# icaRUSv0_2.net
KiCad netlist of a schematic drawn in Altium Designer
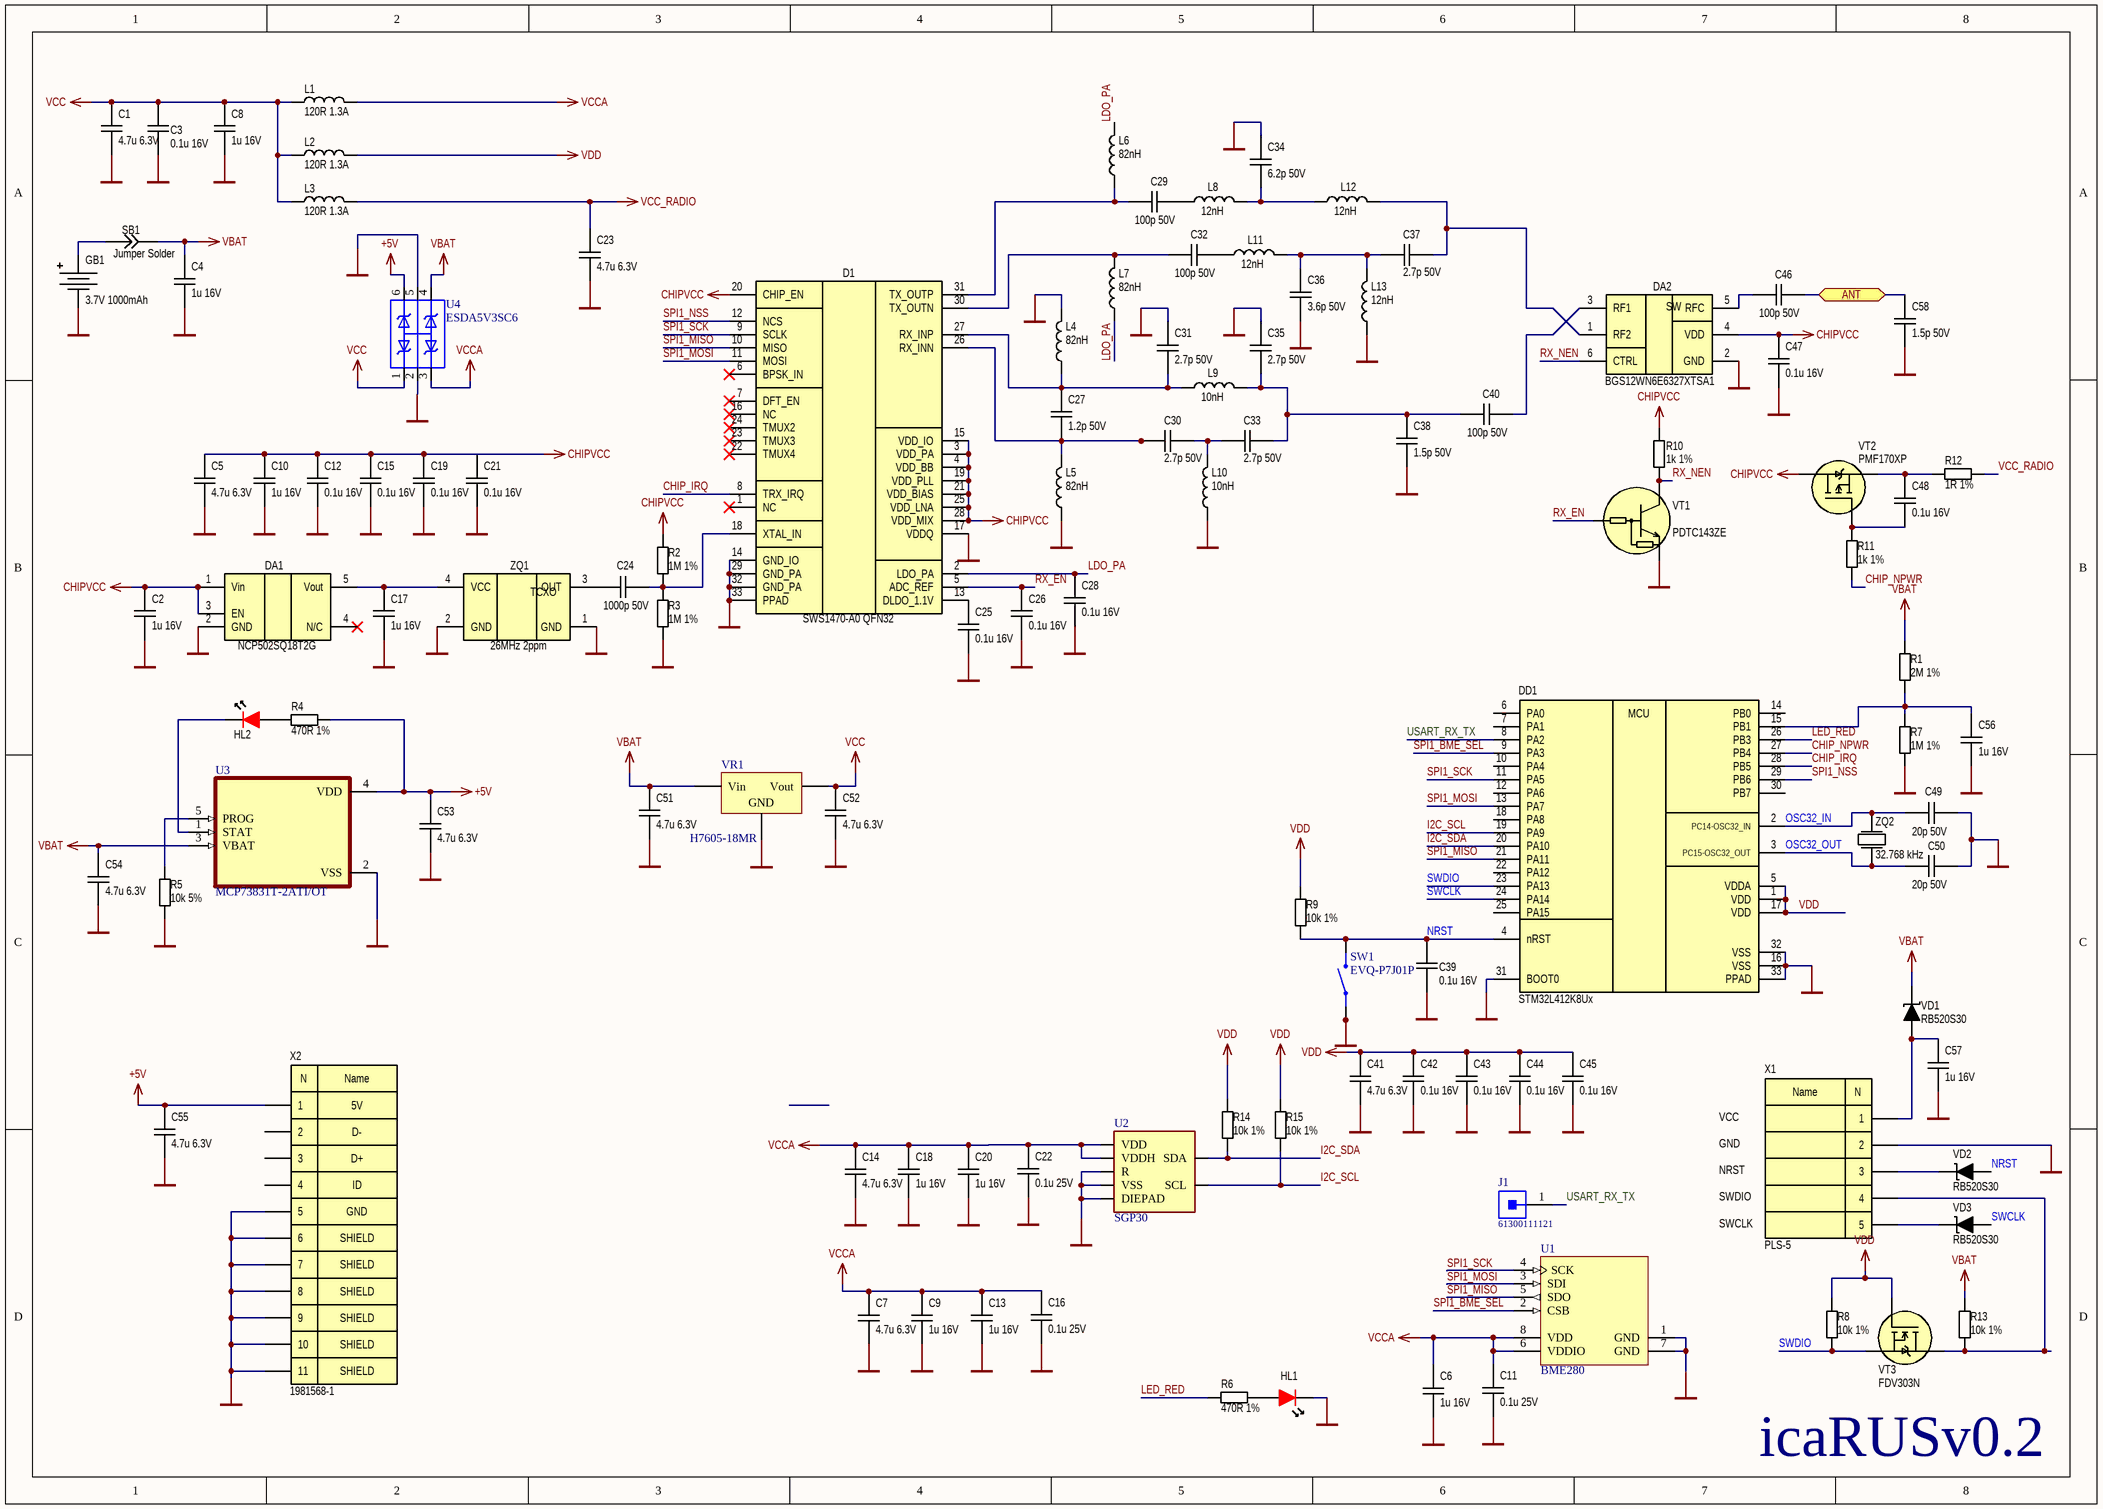
[diagram p0: icaRUSv0.2.SchDoc]

(export (version "E")
  (design (tool "Eeschema 10.0.6"))
  (components
    (comp (ref "C1")
      (value "4.7u 6.3V")
      (footprint "C0402")
      (description "CAP CER 4.7UF 6.3V X5R 0402")
      (fields (field (name "PARTNUMBER") "CC0402KRX5R5BB475"))
      (libsource (lib "Capacitors") (part "CC0402KRX5R5BB475"))
    )
    (comp (ref "C2")
      (value "1u 16V")
      (footprint "C0402")
      (description "CAP CER 1UF 16V X5R 0402")
      (fields (field (name "PARTNUMBER") "CC0402KRX5R7BB105"))
      (libsource (lib "Capacitors") (part "CC0402KRX5R7BB105"))
    )
    (comp (ref "C3")
      (value "0.1u 16V")
      (footprint "C0402")
      (description "CERCAP 0.1/16V 0402 KX7R")
      (fields (field (name "PARTNUMBER") "CC0402KRX7R7BB104"))
      (libsource (lib "Capacitors") (part "CC0603KRX7R7BB104"))
    )
    (comp (ref "C4")
      (value "1u 16V")
      (footprint "C0402")
      (description "CAP CER 1UF 16V X5R 0402")
      (fields (field (name "PARTNUMBER") "CC0402KRX5R7BB105"))
      (libsource (lib "Capacitors") (part "CC0603KRX7R7BB105"))
    )
    (comp (ref "C5")
      (value "4.7u 6.3V")
      (footprint "C0402")
      (description "CAP CER 4.7UF 6.3V X5R 0402")
      (fields (field (name "PARTNUMBER") "CC0402KRX5R5BB475"))
      (libsource (lib "Capacitors") (part "CC0402KRX5R5BB475"))
    )
    (comp (ref "C6")
      (value "1u 16V")
      (footprint "C0402")
      (description "CAP CER 1UF 16V X5R 0402")
      (fields (field (name "PARTNUMBER") "CC0402KRX5R7BB105"))
      (libsource (lib "Capacitors") (part "CC0402KRX7R8BB104"))
    )
    (comp (ref "C7")
      (value "4.7u 6.3V")
      (footprint "C0402")
      (description "CAP CER 4.7UF 6.3V X5R 0402")
      (fields (field (name "PARTNUMBER") "CC0402KRX5R5BB475"))
      (libsource (lib "Capacitors") (part "CC0402KRX5R5BB475"))
    )
    (comp (ref "C8")
      (value "1u 16V")
      (footprint "C0402")
      (description "CAP CER 1UF 16V X5R 0402")
      (fields (field (name "PARTNUMBER") "CC0402KRX5R7BB105"))
      (libsource (lib "Capacitors") (part "CC0603KRX7R7BB105"))
    )
    (comp (ref "C9")
      (value "1u 16V")
      (footprint "C0402")
      (description "CAP CER 1UF 16V X5R 0402")
      (fields (field (name "PARTNUMBER") "CC0402KRX5R7BB105"))
      (libsource (lib "Capacitors") (part "CC0402KRX7R8BB104"))
    )
    (comp (ref "C10")
      (value "1u 16V")
      (footprint "C0402")
      (description "CAP CER 1UF 16V X5R 0402")
      (fields (field (name "PARTNUMBER") "CC0402KRX5R7BB105"))
      (libsource (lib "Capacitors") (part "CC0402KRX7R8BB104"))
    )
    (comp (ref "C11")
      (value "0.1u 25V")
      (footprint "C0402")
      (description "CAP CER 0.1UF 25V X7R 0402")
      (fields (field (name "PARTNUMBER") "CC0402KRX7R8BB104"))
      (libsource (lib "Capacitors") (part "CC0402KRX7R8BB104"))
    )
    (comp (ref "C12")
      (value "0.1u 16V")
      (footprint "C0402")
      (description "CERCAP 0.1/16V 0402 KX7R")
      (fields (field (name "PARTNUMBER") "CC0402KRX7R7BB104"))
      (libsource (lib "Capacitors") (part "CC0402KRX7R8BB104"))
    )
    (comp (ref "C13")
      (value "1u 16V")
      (footprint "C0402")
      (description "CAP CER 1UF 16V X5R 0402")
      (fields (field (name "PARTNUMBER") "CC0402KRX5R7BB105"))
      (libsource (lib "Capacitors") (part "CC0402KRX7R8BB104"))
    )
    (comp (ref "C14")
      (value "4.7u 6.3V")
      (footprint "C0402")
      (description "CAP CER 4.7UF 6.3V X5R 0402")
      (fields (field (name "PARTNUMBER") "CC0402KRX5R5BB475"))
      (libsource (lib "Capacitors") (part "CC0402KRX5R5BB475"))
    )
    (comp (ref "C15")
      (value "0.1u 16V")
      (footprint "C0402")
      (description "CERCAP 0.1/16V 0402 KX7R")
      (fields (field (name "PARTNUMBER") "CC0402KRX7R7BB104"))
      (libsource (lib "Capacitors") (part "CC0402KRX7R8BB104"))
    )
    (comp (ref "C16")
      (value "0.1u 25V")
      (footprint "C0402")
      (description "CAP CER 0.1UF 25V X7R 0402")
      (fields (field (name "PARTNUMBER") "CC0402KRX7R8BB104"))
      (libsource (lib "Capacitors") (part "CC0402KRX7R8BB104"))
    )
    (comp (ref "C17")
      (value "1u 16V")
      (footprint "C0402")
      (description "CAP CER 1UF 16V X5R 0402")
      (fields (field (name "PARTNUMBER") "CC0402KRX5R7BB105"))
      (libsource (lib "Capacitors") (part "CC0402KRX5R7BB105"))
    )
    (comp (ref "C18")
      (value "1u 16V")
      (footprint "C0402")
      (description "CAP CER 1UF 16V X5R 0402")
      (fields (field (name "PARTNUMBER") "CC0402KRX5R7BB105"))
      (libsource (lib "Capacitors") (part "CC0402KRX7R8BB104"))
    )
    (comp (ref "C19")
      (value "0.1u 16V")
      (footprint "C0402")
      (description "CERCAP 0.1/16V 0402 KX7R")
      (fields (field (name "PARTNUMBER") "CC0402KRX7R7BB104"))
      (libsource (lib "Capacitors") (part "CC0402KRX7R8BB104"))
    )
    (comp (ref "C20")
      (value "1u 16V")
      (footprint "C0402")
      (description "CAP CER 1UF 16V X5R 0402")
      (fields (field (name "PARTNUMBER") "CC0402KRX5R7BB105"))
      (libsource (lib "Capacitors") (part "CC0402KRX7R8BB104"))
    )
    (comp (ref "C21")
      (value "0.1u 16V")
      (footprint "C0402")
      (description "CERCAP 0.1/16V 0402 KX7R")
      (fields (field (name "PARTNUMBER") "CC0402KRX7R7BB104"))
      (libsource (lib "Capacitors") (part "CC0402KRX7R8BB104"))
    )
    (comp (ref "C22")
      (value "0.1u 25V")
      (footprint "C0402")
      (description "CAP CER 0.1UF 25V X7R 0402")
      (fields (field (name "PARTNUMBER") "CC0402KRX7R8BB104"))
      (libsource (lib "Capacitors") (part "CC0402KRX7R8BB104"))
    )
    (comp (ref "C23")
      (value "4.7u 6.3V")
      (footprint "C0402")
      (description "CAP CER 4.7UF 6.3V X5R 0402")
      (fields (field (name "PARTNUMBER") "CC0402KRX5R5BB475"))
      (libsource (lib "Capacitors") (part "CC0402KRX5R5BB475"))
    )
    (comp (ref "C24")
      (value "1000p 50V")
      (footprint "C0402")
      (description "CAP CER 1000PF 1% 50V C0G/NPO 0402")
      (fields (field (name "PARTNUMBER") "0402N102F500LT"))
      (libsource (lib "Capacitors") (part "CC0402JRX7R9BB102"))
    )
    (comp (ref "C25")
      (value "0.1u 16V")
      (footprint "C0402")
      (description "CERCAP 0.1/16V 0402 KX7R")
      (fields (field (name "PARTNUMBER") "CC0402KRX7R7BB104"))
      (libsource (lib "Capacitors") (part "CC0402KRX7R8BB104"))
    )
    (comp (ref "C26")
      (value "0.1u 16V")
      (footprint "C0402")
      (description "CERCAP 0.1/16V 0402 KX7R")
      (fields (field (name "PARTNUMBER") "CC0402KRX7R7BB104"))
      (libsource (lib "Capacitors") (part "CC0402KRX7R8BB104"))
    )
    (comp (ref "C27")
      (value "1.2p 50V")
      (footprint "C0402")
      (description "CAP CER 1.2PF 50V NPO 0402")
      (fields (field (name "PARTNUMBER") "CC0402BRNPO9BN1R2"))
      (libsource (lib "Capacitors") (part "CC0402BRNPO9BN1R0"))
    )
    (comp (ref "C28")
      (value "0.1u 16V")
      (footprint "C0402")
      (description "CERCAP 0.1/16V 0402 KX7R")
      (fields (field (name "PARTNUMBER") "CC0402KRX7R7BB104"))
      (libsource (lib "Capacitors") (part "CC0402KRX7R8BB104"))
    )
    (comp (ref "C29")
      (value "100p 50V")
      (footprint "C0402")
      (description "CAP CER 100PF 50V C0G/NPO 0402")
      (fields (field (name "PARTNUMBER") "CC0402JRNPO9BN101"))
      (libsource (lib "Capacitors") (part "CC0402JRNPO9BN101"))
    )
    (comp (ref "C30")
      (value "2.7p 50V")
      (footprint "C0402")
      (description "CAP CER 2.7PF 50V C0G/NPO 0402")
      (fields (field (name "PARTNUMBER") "CC0402BRNPO9BN2R7"))
      (libsource (lib "Capacitors") (part "CC0402BRNPO9BN2R0"))
    )
    (comp (ref "C31")
      (value "2.7p 50V")
      (footprint "C0402")
      (description "CAP CER 2.7PF 50V C0G/NPO 0402")
      (fields (field (name "PARTNUMBER") "CC0402BRNPO9BN2R7"))
      (libsource (lib "Capacitors") (part "CC0402BRNPO9BN2R0"))
    )
    (comp (ref "C32")
      (value "100p 50V")
      (footprint "C0402")
      (description "CAP CER 100PF 50V C0G/NPO 0402")
      (fields (field (name "PARTNUMBER") "CC0402JRNPO9BN101"))
      (libsource (lib "Capacitors") (part "CC0402JRNPO9BN101"))
    )
    (comp (ref "C33")
      (value "2.7p 50V")
      (footprint "C0402")
      (description "CAP CER 2.7PF 50V C0G/NPO 0402")
      (fields (field (name "PARTNUMBER") "CC0402BRNPO9BN2R7"))
      (libsource (lib "Capacitors") (part "CC0402BRNPO9BN2R0"))
    )
    (comp (ref "C34")
      (value "6.2p 50V")
      (footprint "C0402")
      (description "CAP CER 6.2PF 50V NPO 0402")
      (fields (field (name "PARTNUMBER") "CC0402CRNPO9BN6R2"))
      (libsource (lib "Capacitors") (part "CC0402CRNPO9BN6R2"))
    )
    (comp (ref "C35")
      (value "2.7p 50V")
      (footprint "C0402")
      (description "CAP CER 2.7PF 50V C0G/NPO 0402")
      (fields (field (name "PARTNUMBER") "CC0402BRNPO9BN2R7"))
      (libsource (lib "Capacitors") (part "CC0402BRNPO9BN2R0"))
    )
    (comp (ref "C36")
      (value "3.6p 50V")
      (footprint "C0402")
      (description "CAP CER 3.6PF 50V NPO 0402")
      (fields (field (name "PARTNUMBER") "CC0402BRNPO9BN3R6"))
      (libsource (lib "Capacitors") (part "CC0402BRNPO9BN3R6"))
    )
    (comp (ref "C37")
      (value "2.7p 50V")
      (footprint "C0402")
      (description "CAP CER 2.7pF 50V NPO 0402")
      (fields (field (name "PARTNUMBER") "CC0402BRNPO9BN2R7"))
      (libsource (lib "Capacitors") (part "CC0402BRNPO9BN3R6"))
    )
    (comp (ref "C38")
      (value "1.5p 50V")
      (footprint "C0402")
      (description "CAP CER 1.5PF 50V NPO 0402")
      (fields (field (name "PARTNUMBER") "CC0402BRNPO9BN1R5"))
      (libsource (lib "Capacitors") (part "CC0402BRNPO9BN1R0"))
    )
    (comp (ref "C39")
      (value "0.1u 16V")
      (footprint "C0402")
      (description "CERCAP 0.1/16V 0402 KX7R")
      (fields (field (name "PARTNUMBER") "CC0402KRX7R7BB104"))
      (libsource (lib "Capacitors") (part "CC0402KRX7R8BB104"))
    )
    (comp (ref "C40")
      (value "100p 50V")
      (footprint "C0402")
      (description "CAP CER 100PF 50V C0G/NPO 0402")
      (fields (field (name "PARTNUMBER") "CC0402JRNPO9BN101"))
      (libsource (lib "Capacitors") (part "CC0402JRNPO9BN101"))
    )
    (comp (ref "C41")
      (value "4.7u 6.3V")
      (footprint "C0402")
      (description "CAP CER 4.7UF 6.3V X5R 0402")
      (fields (field (name "PARTNUMBER") "CC0402KRX5R5BB475"))
      (libsource (lib "Capacitors") (part "CC0402KRX5R5BB475"))
    )
    (comp (ref "C42")
      (value "0.1u 16V")
      (footprint "C0402")
      (description "CERCAP 0.1/16V 0402 KX7R")
      (fields (field (name "PARTNUMBER") "CC0402KRX7R7BB104"))
      (libsource (lib "Capacitors") (part "CC0402KRX7R8BB104"))
    )
    (comp (ref "C43")
      (value "0.1u 16V")
      (footprint "C0402")
      (description "CERCAP 0.1/16V 0402 KX7R")
      (fields (field (name "PARTNUMBER") "CC0402KRX7R7BB104"))
      (libsource (lib "Capacitors") (part "CC0402KRX7R8BB104"))
    )
    (comp (ref "C44")
      (value "0.1u 16V")
      (footprint "C0402")
      (description "CERCAP 0.1/16V 0402 KX7R")
      (fields (field (name "PARTNUMBER") "CC0402KRX7R7BB104"))
      (libsource (lib "Capacitors") (part "CC0402KRX7R8BB104"))
    )
    (comp (ref "C45")
      (value "0.1u 16V")
      (footprint "C0402")
      (description "CERCAP 0.1/16V 0402 KX7R")
      (fields (field (name "PARTNUMBER") "CC0402KRX7R7BB104"))
      (libsource (lib "Capacitors") (part "CC0402KRX7R8BB104"))
    )
    (comp (ref "C46")
      (value "100p 50V")
      (footprint "C0402")
      (description "CAP CER 100PF 50V C0G/NPO 0402")
      (fields (field (name "PARTNUMBER") "CC0402JRNPO9BN101"))
      (libsource (lib "Capacitors") (part "CC0402JRNPO9BN101"))
    )
    (comp (ref "C47")
      (value "0.1u 16V")
      (footprint "C0402")
      (description "CERCAP 0.1/16V 0402 KX7R")
      (fields (field (name "PARTNUMBER") "CC0402KRX7R7BB104"))
      (libsource (lib "Capacitors") (part "CC0402KRX7R8BB104"))
    )
    (comp (ref "C48")
      (value "0.1u 16V")
      (footprint "C0402")
      (description "CERCAP 0.1/16V 0402 KX7R")
      (fields (field (name "PARTNUMBER") "CC0402KRX7R7BB104"))
      (libsource (lib "Capacitors") (part "CC0402KRX7R8BB104"))
    )
    (comp (ref "C49")
      (value "20p 50V")
      (footprint "C0402")
      (description "CAP CER 20PF 50V C0G/NPO 0402")
      (fields (field (name "PARTNUMBER") "CC0402JRNPO9BN200"))
      (libsource (lib "Capacitors") (part "CC0402JRNPO9BN200"))
    )
    (comp (ref "C50")
      (value "20p 50V")
      (footprint "C0402")
      (description "CAP CER 20PF 50V C0G/NPO 0402")
      (fields (field (name "PARTNUMBER") "CC0402JRNPO9BN200"))
      (libsource (lib "Capacitors") (part "CC0402JRNPO9BN200"))
    )
    (comp (ref "C51")
      (value "4.7u 6.3V")
      (footprint "C0402")
      (description "CAP CER 4.7UF 6.3V X5R 0402")
      (fields (field (name "PARTNUMBER") "CC0402KRX5R5BB475"))
      (libsource (lib "Capacitors") (part "CC0402KRX5R5BB475"))
    )
    (comp (ref "C52")
      (value "4.7u 6.3V")
      (footprint "C0402")
      (description "CAP CER 4.7UF 6.3V X5R 0402")
      (fields (field (name "PARTNUMBER") "CC0402KRX5R5BB475"))
      (libsource (lib "Capacitors") (part "CC0402KRX5R5BB475"))
    )
    (comp (ref "C53")
      (value "4.7u 6.3V")
      (footprint "C0402")
      (description "CAP CER 4.7UF 6.3V X5R 0402")
      (fields (field (name "PARTNUMBER") "CC0402KRX5R5BB475"))
      (libsource (lib "Capacitors") (part "CC0402KRX5R5BB475"))
    )
    (comp (ref "C54")
      (value "4.7u 6.3V")
      (footprint "C0402")
      (description "CAP CER 4.7UF 6.3V X5R 0402")
      (fields (field (name "PARTNUMBER") "CC0402KRX5R5BB475"))
      (libsource (lib "Capacitors") (part "CC0402KRX5R5BB475"))
    )
    (comp (ref "C55")
      (value "4.7u 6.3V")
      (footprint "C0402")
      (description "CAP CER 4.7UF 6.3V X5R 0402")
      (fields (field (name "PARTNUMBER") "CC0402KRX5R5BB475"))
      (libsource (lib "Capacitors") (part "CC0402KRX5R5BB475"))
    )
    (comp (ref "C56")
      (value "1u 16V")
      (footprint "C0402")
      (description "CAP CER 1UF 16V X5R 0402")
      (fields (field (name "PARTNUMBER") "CC0402KRX5R7BB105"))
      (libsource (lib "Capacitors") (part "CC0402KRX7R8BB104"))
    )
    (comp (ref "C57")
      (value "1u 16V")
      (footprint "C0402")
      (description "CAP CER 1UF 16V X5R 0402")
      (fields (field (name "PARTNUMBER") "CC0402KRX5R7BB105"))
      (libsource (lib "Capacitors") (part "CC0402KRX7R8BB104"))
    )
    (comp (ref "C58")
      (value "1.5p 50V")
      (footprint "C0402")
      (description "CAP CER 1.5PF 50V NPO 0402")
      (fields (field (name "PARTNUMBER") "CC0402BRNPO9BN1R5"))
      (libsource (lib "Capacitors") (part "CC0402BRNPO9BN1R0"))
    )
    (comp (ref "D1")
      (value "SWS1470-A0 QFN32")
      (footprint "QFN32")
      (description "Waviot NB-Fi RF Transceiver QFN32")
      (libsource (lib "Integrated Circuits (ICs)") (part "SWS1470-A0 QFN32"))
    )
    (comp (ref "DA1")
      (value "NCP502SQ18T2G")
      (footprint "SOT323-5")
      (description "IC REG LINEAR 1.8V 80MA SC88A")
      (libsource (lib "Integrated Circuits (ICs)") (part "NCP502SQ18T2G"))
    )
    (comp (ref "DA2")
      (value "BGS12WN6E6327XTSA1")
      (footprint "6-XFDFN")
      (description "RF Switch IC WLAN SPDT 50Ohm PG-TSNP-6-10")
      (libsource (lib "RF, IF and RFID") (part "BGS12WN6E6327XTSA1"))
    )
    (comp (ref "DD1")
      (value "STM32L412K8Ux")
      (footprint "UFQFPN32")
      (fields (field (name "PARTNUMBER") "STM32L412KBUx"))
      (libsource (lib "Integrated Circuits (ICs)") (part "STM32L412K8Ux"))
    )
    (comp (ref "GB1")
      (value "3.7V 1000mAh")
      (footprint "LP753440 3.7V 1000mAh with PCM")
      (description "LiPoly Battery LP753440 3.7V 1000mAh with PCM")
      (fields (field (name "PARTNUMBER") "LP753440"))
      (libsource (lib "Batteries") (part "CR17505"))
    )
    (comp (ref "HL1")
      (value "RED")
      (footprint "LED0603_RED")
      (description "LED Red 0603")
      (fields (field (name "PARTNUMBER") "FYLS-0603URC"))
      (libsource (lib "Diodes") (part "FYLS-0603URC"))
    )
    (comp (ref "HL2")
      (value "RED")
      (footprint "LED0603_RED")
      (description "LED Red 0603")
      (fields (field (name "PARTNUMBER") "FYLS-0603URC"))
      (libsource (lib "Diodes") (part "FYLS-0603URC"))
    )
    (comp (ref "J1")
      (value "61300111121")
      (footprint "61300111121")
      (description "THT Vertical Pin Header WR-PHD, Pitch 2.54 mm, Single Row, 1 pins")
      (fields (field (name "MANUFACTURER") "Wurth Elektronik") (field (name "PUBLISHER") "WurthElektronik"))
      (libsource (lib "Altium Content Vault") (part "WE-CN-1P-M-R1"))
    )
    (comp (ref "L1")
      (value "120R 1.3A")
      (footprint "L0402_BEAD")
      (description "FERRITE BEAD 120 OHM 0402 1LN")
      (fields (field (name "PARTNUMBER") "BLM15PD121SZ1D"))
      (libsource (lib "Filters") (part "BLM15PD121SZ1D"))
    )
    (comp (ref "L2")
      (value "120R 1.3A")
      (footprint "L0402_BEAD")
      (description "FERRITE BEAD 120 OHM 0402 1LN")
      (fields (field (name "PARTNUMBER") "BLM15PD121SZ1D"))
      (libsource (lib "Filters") (part "BLM15PD121SZ1D"))
    )
    (comp (ref "L3")
      (value "120R 1.3A")
      (footprint "L0402_BEAD")
      (description "FERRITE BEAD 120 OHM 0402 1LN")
      (fields (field (name "PARTNUMBER") "BLM15PD121SZ1D"))
      (libsource (lib "Filters") (part "BLM15PD121SZ1D"))
    )
    (comp (ref "L4")
      (value "82nH")
      (footprint "L0402")
      (description "FIXED IND 82NH 130MA 2.24 OHM")
      (fields (field (name "PARTNUMBER") "LQW15AN82NG00D"))
      (libsource (lib "Inductors, Coils, Chokes") (part "LQW15AN82NG00D"))
    )
    (comp (ref "L5")
      (value "82nH")
      (footprint "L0402")
      (description "FIXED IND 82NH 130MA 2.24 OHM")
      (fields (field (name "PARTNUMBER") "LQW15AN82NG00D"))
      (libsource (lib "Inductors, Coils, Chokes") (part "LQW15AN82NG00D"))
    )
    (comp (ref "L6")
      (value "82nH")
      (footprint "L0402")
      (description "FIXED IND 82NH 130MA 2.24 OHM")
      (fields (field (name "PARTNUMBER") "LQW15AN82NG00D"))
      (libsource (lib "Inductors, Coils, Chokes") (part "LQW15AN82NG00D"))
    )
    (comp (ref "L7")
      (value "82nH")
      (footprint "L0402")
      (description "FIXED IND 82NH 130MA 2.24 OHM")
      (fields (field (name "PARTNUMBER") "LQW15AN82NG00D"))
      (libsource (lib "Inductors, Coils, Chokes") (part "LQW15AN82NG00D"))
    )
    (comp (ref "L8")
      (value "12nH")
      (footprint "L0402")
      (description "FIXED IND 12NH 500MA 140 MOHM")
      (fields (field (name "PARTNUMBER") "LQW15AN12NG00D"))
      (libsource (lib "Inductors, Coils, Chokes") (part "LQW15AN12NG00D"))
    )
    (comp (ref "L9")
      (value "10nH")
      (footprint "L0402")
      (description "FIXED IND 10NH 500MA 170 MOHM")
      (fields (field (name "PARTNUMBER") "LQW15AN10NG00D"))
      (libsource (lib "") (part "LQW15AN10NG00D_1"))
    )
    (comp (ref "L10")
      (value "10nH")
      (footprint "L0402")
      (description "FIXED IND 10NH 500MA 170 MOHM")
      (fields (field (name "PARTNUMBER") "LQW15AN10NG00D"))
      (libsource (lib "Inductors, Coils, Chokes") (part "LQW15AN10NG00D"))
    )
    (comp (ref "L11")
      (value "12nH")
      (footprint "L0402")
      (description "FIXED IND 12NH 500MA 140 MOHM")
      (fields (field (name "PARTNUMBER") "LQW15AN12NG00D"))
      (libsource (lib "Inductors, Coils, Chokes") (part "LQW15AN12NG00D"))
    )
    (comp (ref "L12")
      (value "12nH")
      (footprint "L0402")
      (description "FIXED IND 12NH 500MA 140 MOHM")
      (fields (field (name "PARTNUMBER") "LQW15AN12NG00D"))
      (libsource (lib "Inductors, Coils, Chokes") (part "LQW15AN12NG00D"))
    )
    (comp (ref "L13")
      (value "12nH")
      (footprint "L0402")
      (description "FIXED IND 12NH 500MA 140 MOHM")
      (fields (field (name "PARTNUMBER") "LQW15AN12NG00D"))
      (libsource (lib "") (part "LQW15AN12NG00D_1"))
    )
    (comp (ref "R1")
      (value "2M 1%")
      (footprint "R0402")
      (description "RES SMD 2M OHM 1% 1/16W 0402")
      (fields (field (name "PARTNUMBER") "RC0402FR-072ML"))
      (libsource (lib "") (part "RC0402FR-071ML_1"))
    )
    (comp (ref "R2")
      (value "1M 1%")
      (footprint "R0402")
      (description "RES SMD 1M OHM 1% 1/16W 0402")
      (fields (field (name "PARTNUMBER") "RC0402FR-071ML"))
      (libsource (lib "") (part "RC0402FR-071ML_1"))
    )
    (comp (ref "R3")
      (value "1M 1%")
      (footprint "R0402")
      (description "RES SMD 1M OHM 1% 1/16W 0402")
      (fields (field (name "PARTNUMBER") "RC0402FR-071ML"))
      (libsource (lib "") (part "RC0402FR-071ML_1"))
    )
    (comp (ref "R4")
      (value "470R 1%")
      (footprint "R0402")
      (description "RES 0603 470R 1%")
      (fields (field (name "PARTNUMBER") "RC0603FR-07470RL"))
      (libsource (lib "Resistors") (part "RC0603FR-07200RL"))
    )
    (comp (ref "R5")
      (value "10k 5%")
      (footprint "R0402")
      (description "RES SMD 10k OHM 5% 1/16W 0402")
      (fields (field (name "PARTNUMBER") "RC0402JR-0710KL"))
      (libsource (lib "Resistors") (part "RC0402FR-071ML"))
    )
    (comp (ref "R6")
      (value "470R 1%")
      (footprint "R0402")
      (description "RES 0603 470R 1%")
      (fields (field (name "PARTNUMBER") "RC0603FR-07470RL"))
      (libsource (lib "Resistors") (part "RC0603FR-07200RL"))
    )
    (comp (ref "R7")
      (value "1M 1%")
      (footprint "R0402")
      (description "RES SMD 1M OHM 1% 1/16W 0402")
      (fields (field (name "PARTNUMBER") "RC0402FR-071ML"))
      (libsource (lib "") (part "RC0402FR-071ML_1"))
    )
    (comp (ref "R8")
      (value "10k 1%")
      (footprint "R0402")
      (description "RES SMD 10K OHM 1% 1/16W 0402")
      (fields (field (name "PARTNUMBER") "RC0402FR-0710KL"))
      (libsource (lib "Resistors") (part "RC0402FR-0710KL"))
    )
    (comp (ref "R9")
      (value "10k 1%")
      (footprint "R0402")
      (description "RES SMD 10K OHM 1% 1/16W 0402")
      (fields (field (name "PARTNUMBER") "RC0402FR-0710KL"))
      (libsource (lib "") (part "RC0402FR-0710KL_1"))
    )
    (comp (ref "R10")
      (value "1k 1%")
      (footprint "R0402")
      (description "RES SMD 1K OHM 1% 1/16W 0402")
      (fields (field (name "PARTNUMBER") "RC0402FR-071KL"))
      (libsource (lib "Resistors") (part "RC0402FR-071KL"))
    )
    (comp (ref "R11")
      (value "1k 1%")
      (footprint "R0402")
      (description "RES SMD 1K OHM 1% 1/16W 0402")
      (fields (field (name "PARTNUMBER") "RC0402FR-071KL"))
      (libsource (lib "Resistors") (part "RC0402FR-071KL"))
    )
    (comp (ref "R12")
      (value "1R 1%")
      (footprint "R0402")
      (description "RES SMD 1 OHM 1% 1/16W 0402")
      (fields (field (name "PARTNUMBER") "RC0402FR-071RL"))
      (libsource (lib "Resistors") (part "RC0402FR-071RL"))
    )
    (comp (ref "R13")
      (value "10k 1%")
      (footprint "R0402")
      (description "RES SMD 10K OHM 1% 1/16W 0402")
      (fields (field (name "PARTNUMBER") "RC0402FR-0710KL"))
      (libsource (lib "Resistors") (part "RC0402FR-0710KL"))
    )
    (comp (ref "R14")
      (value "10k 1%")
      (footprint "R0402")
      (description "RES SMD 10K OHM 1% 1/16W 0402")
      (fields (field (name "PARTNUMBER") "RC0402FR-0710KL"))
      (libsource (lib "") (part "RC0402FR-0710KL_1"))
    )
    (comp (ref "R15")
      (value "10k 1%")
      (footprint "R0402")
      (description "RES SMD 10K OHM 1% 1/16W 0402")
      (fields (field (name "PARTNUMBER") "RC0402FR-0710KL"))
      (libsource (lib "") (part "RC0402FR-0710KL_1"))
    )
    (comp (ref "SB1")
      (value "Jumper Solder")
      (footprint "SB0805")
      (libsource (lib "Connectors") (part "Jumper Solder"))
    )
    (comp (ref "SW1")
      (value "EVQ-P7J01P")
      (footprint "EVQ-P7J01P:SW_EVQ-P7J01P")
      (description "Tactile Switch SPST-NO Side Actuated Surface Mount, Right Angle")
      (fields (field (name "MF") "Panasonic Electronic"))
      (libsource (lib "EVQ-P7J01P") (part "EVQ-P7J01P"))
    )
    (comp (ref "U1")
      (value "BME280")
      (footprint "BOSC-BME280-8_V")
      (fields (field (name "MANUFACTURER") "Bosch Sensortec"))
      (libsource (lib "Altium Content Vault") (part "BOSC-BME280-8"))
    )
    (comp (ref "U2")
      (value "SGP30")
      (footprint "SGP30:SGP30")
      (fields (field (name "MF") "{'manufacturer': u'Sensirion AG'}"))
      (libsource (lib "*") (part "SGP30"))
    )
    (comp (ref "U3")
      (value "MCP73831T-2ATI/OT")
      (footprint "SOT23-5")
      (description "Charger IC Lithium Ion/Polymer SOT-23-5")
      (fields (field (name "MF") "Microchip"))
      (libsource (lib "MCP73831T-2ATI_OT") (part "MCP73831T-2ATI/OT"))
    )
    (comp (ref "U4")
      (value "ESDA5V3SC6")
      (footprint "SOT23-6L")
      (description "Clamp Ipp Tvs Diode Surface Mount SOT-23-6")
      (fields (field (name "MF") "STMicroelectronics"))
      (libsource (lib "ESDA5V3SC6") (part "ESDA5V3SC6"))
    )
    (comp (ref "VD1")
      (value "RB520S30")
      (footprint "SOD523F")
      (description "RECTIFIER DIODE, SCHOTTKY, 0.2A")
      (libsource (lib "Discrete Semiconductor Products") (part "RB520S30"))
    )
    (comp (ref "VD2")
      (value "RB520S30")
      (footprint "SOD523F")
      (description "RECTIFIER DIODE, SCHOTTKY, 0.2A")
      (libsource (lib "Discrete Semiconductor Products") (part "RB520S30"))
    )
    (comp (ref "VD3")
      (value "RB520S30")
      (footprint "SOD523F")
      (description "RECTIFIER DIODE, SCHOTTKY, 0.2A")
      (libsource (lib "Discrete Semiconductor Products") (part "RB520S30"))
    )
    (comp (ref "VR1")
      (value "H7605-18MR")
      (footprint "SOT23-3L")
      (description "Voltage Regulator H7605-18MR")
      (libsource (lib "Miscellaneous Devices") (part "Volt Reg"))
    )
    (comp (ref "VT1")
      (value "PDTC143ZE")
      (footprint "SOT416")
      (description "SMALL SIGNAL BIPOLAR TRANSISTOR")
      (libsource (lib "Discrete Semiconductor Products") (part "PDTC143ZE"))
    )
    (comp (ref "VT2")
      (value "PMF170XP")
      (footprint "SOT323")
      (description "MOSFET P-CH 20V 1A SOT323")
      (libsource (lib "Discrete Semiconductor Products") (part "PMF170XP"))
    )
    (comp (ref "VT3")
      (value "FDV303N")
      (footprint "SOT23-3L")
      (description "MOSFET N-CH 25V 680MA SOT-23")
      (libsource (lib "Discrete Semiconductor Products") (part "FDV303N"))
    )
    (comp (ref "X1")
      (value "PLS-5")
      (footprint "PLS-5-2.54-PCB")
      (description "PLS-5-2.54")
      (libsource (lib "Connectors") (part "PLS-5"))
    )
    (comp (ref "X2")
      (value "1981568-1")
      (footprint "1981568-1")
      (description "CONN RCPT USB2.0 MICRO B SMD R/A")
      (libsource (lib "Connectors") (part "1981568-1"))
    )
    (comp (ref "ZQ1")
      (value "26MHz 2ppm")
      (footprint "QSMD2.0x1.6x0.7")
      (description "TCXO Oscillator 4-pin")
      (fields (field (name "PARTNUMBER") "NT2016SA-26.000000MHZ-NBG2"))
      (libsource (lib "Crystals, Oscillators, Resonators") (part "NT2016SA-26.000000MHZ-NBG2"))
    )
    (comp (ref "ZQ2")
      (value "32.768 kHz")
      (footprint "QSMD3.2X1.5X0.8")
      (description "CRYSTAL 32.768KHZ 12.5PF SMD")
      (fields (field (name "PARTNUMBER") "NX3215SA-32.768K-EXS00A"))
      (libsource (lib "Crystals, Oscillators, Resonators") (part "NX3215SA-32.768K-EXS00A"))
    )
  )
  (nets
    (net (code "1") (name "+5V") (class "Default")
      (node (ref "C53") (pin "1") (pinfunction "1_1") (pintype "passive"))
      (node (ref "C55") (pin "1") (pinfunction "1_1") (pintype "passive"))
      (node (ref "R4") (pin "1") (pinfunction "1_1") (pintype "passive"))
      (node (ref "U3") (pin "4") (pinfunction "VDD_4") (pintype "power_in"))
      (node (ref "U4") (pin "6") (pinfunction "K4_6") (pintype "bidirectional"))
      (node (ref "X2") (pin "1") (pinfunction "1_1") (pintype "passive"))
    )
    (net (code "2") (name "/ANT") (class "Default")
      (node (ref "C46") (pin "2") (pinfunction "2_2") (pintype "passive"))
      (node (ref "C58") (pin "1") (pinfunction "1_1") (pintype "passive"))
    )
    (net (code "3") (name "/CHIP_IRQ") (class "Default")
      (node (ref "D1") (pin "8") (pinfunction "TRX_IRQ_8") (pintype "passive"))
      (node (ref "DD1") (pin "28") (pinfunction "PB5_28") (pintype "passive"))
    )
    (net (code "4") (name "/CHIP_NPWR") (class "Default")
      (node (ref "DD1") (pin "27") (pinfunction "PB4_27") (pintype "passive"))
      (node (ref "R11") (pin "1") (pinfunction "1_1") (pintype "passive"))
    )
    (net (code "5") (name "/I2C_SCL") (class "Default")
      (node (ref "DD1") (pin "19") (pinfunction "PA9_19") (pintype "passive"))
      (node (ref "R15") (pin "2") (pinfunction "2_2") (pintype "passive"))
      (node (ref "U2") (pin "6") (pinfunction "SCL_6") (pintype "bidirectional"))
    )
    (net (code "6") (name "/I2C_SDA") (class "Default")
      (node (ref "DD1") (pin "20") (pinfunction "PA10_20") (pintype "passive"))
      (node (ref "R14") (pin "2") (pinfunction "2_2") (pintype "passive"))
      (node (ref "U2") (pin "3") (pinfunction "SDA_3") (pintype "bidirectional"))
    )
    (net (code "7") (name "/LDO_PA") (class "Default")
      (node (ref "C28") (pin "2") (pinfunction "2_2") (pintype "passive"))
      (node (ref "D1") (pin "2") (pinfunction "LDO_PA_2") (pintype "passive"))
      (node (ref "L6") (pin "2") (pinfunction "2_2") (pintype "passive"))
      (node (ref "L7") (pin "1") (pinfunction "1_1") (pintype "passive"))
    )
    (net (code "8") (name "/LED_RED") (class "Default")
      (node (ref "DD1") (pin "26") (pinfunction "PB3_26") (pintype "passive"))
      (node (ref "R6") (pin "2") (pinfunction "2_2") (pintype "passive"))
    )
    (net (code "9") (name "/NRST") (class "Default")
      (node (ref "C39") (pin "1") (pinfunction "1_1") (pintype "passive"))
      (node (ref "DD1") (pin "4") (pinfunction "nRST_4") (pintype "passive"))
      (node (ref "R9") (pin "2") (pinfunction "2_2") (pintype "passive"))
      (node (ref "SW1") (pin "2_1") (pinfunction "2_2_1") (pintype "passive"))
      (node (ref "SW1") (pin "2_2") (pinfunction "2_2_2") (pintype "passive"))
      (node (ref "VD2") (pin "1") (pinfunction "1_1") (pintype "passive"))
    )
    (net (code "10") (name "/OSC32_IN") (class "Default")
      (node (ref "C49") (pin "1") (pinfunction "1_1") (pintype "passive"))
      (node (ref "DD1") (pin "2") (pinfunction "PC14-OSC32_IN_2") (pintype "passive"))
      (node (ref "ZQ2") (pin "1") (pinfunction "1_1") (pintype "passive"))
    )
    (net (code "11") (name "/OSC32_OUT") (class "Default")
      (node (ref "C50") (pin "1") (pinfunction "1_1") (pintype "passive"))
      (node (ref "DD1") (pin "3") (pinfunction "PC15-OSC32_OUT_3") (pintype "passive"))
      (node (ref "ZQ2") (pin "3") (pinfunction "3_3") (pintype "passive"))
    )
    (net (code "12") (name "/RX_EN") (class "Default")
      (node (ref "C26") (pin "2") (pinfunction "2_2") (pintype "passive"))
      (node (ref "D1") (pin "5") (pinfunction "ADC_REF_5") (pintype "passive"))
      (node (ref "VT1") (pin "1") (pinfunction "1_1") (pintype "passive"))
    )
    (net (code "13") (name "/RX_NEN") (class "Default")
      (node (ref "DA2") (pin "6") (pinfunction "CTRL_6") (pintype "passive"))
      (node (ref "R10") (pin "1") (pinfunction "1_1") (pintype "passive"))
      (node (ref "VT1") (pin "3") (pinfunction "3_3") (pintype "passive"))
    )
    (net (code "14") (name "/SPI1_BME_SEL") (class "Default")
      (node (ref "DD1") (pin "9") (pinfunction "PA3_9") (pintype "passive"))
      (node (ref "U1") (pin "2") (pinfunction "CSB_2") (pintype "input"))
    )
    (net (code "15") (name "/SPI1_MISO") (class "Default")
      (node (ref "D1") (pin "10") (pinfunction "MISO_10") (pintype "passive"))
      (node (ref "DD1") (pin "21") (pinfunction "PA11_21") (pintype "passive"))
      (node (ref "U1") (pin "5") (pinfunction "SDO_5") (pintype "output"))
    )
    (net (code "16") (name "/SPI1_MOSI") (class "Default")
      (node (ref "D1") (pin "11") (pinfunction "MOSI_11") (pintype "passive"))
      (node (ref "DD1") (pin "13") (pinfunction "PA7_13") (pintype "passive"))
      (node (ref "U1") (pin "3") (pinfunction "SDI_3") (pintype "input"))
    )
    (net (code "17") (name "/SPI1_NSS") (class "Default")
      (node (ref "D1") (pin "12") (pinfunction "NCS_12") (pintype "passive"))
      (node (ref "DD1") (pin "29") (pinfunction "PB6_29") (pintype "passive"))
    )
    (net (code "18") (name "/SPI1_SCK") (class "Default")
      (node (ref "D1") (pin "9") (pinfunction "SCLK_9") (pintype "passive"))
      (node (ref "DD1") (pin "11") (pinfunction "PA5_11") (pintype "passive"))
      (node (ref "U1") (pin "4") (pinfunction "SCK_4") (pintype "input"))
    )
    (net (code "19") (name "/SWCLK") (class "Default")
      (node (ref "DD1") (pin "24") (pinfunction "PA14_24") (pintype "passive"))
      (node (ref "VD3") (pin "1") (pinfunction "1_1") (pintype "passive"))
    )
    (net (code "20") (name "/SWDIO") (class "Default")
      (node (ref "DD1") (pin "23") (pinfunction "PA13_23") (pintype "passive"))
      (node (ref "R8") (pin "1") (pinfunction "1_1") (pintype "passive"))
      (node (ref "VT3") (pin "2") (pinfunction "S_2") (pintype "passive"))
    )
    (net (code "21") (name "/USART_RX_TX") (class "Default")
      (node (ref "DD1") (pin "8") (pinfunction "PA2_8") (pintype "passive"))
      (node (ref "J1") (pin "1") (pinfunction "1_1") (pintype "passive"))
    )
    (net (code "22") (name "CHIPVCC") (class "Default")
      (node (ref "C10") (pin "2") (pinfunction "2_2") (pintype "passive"))
      (node (ref "C12") (pin "2") (pinfunction "2_2") (pintype "passive"))
      (node (ref "C15") (pin "2") (pinfunction "2_2") (pintype "passive"))
      (node (ref "C19") (pin "2") (pinfunction "2_2") (pintype "passive"))
      (node (ref "C2") (pin "2") (pinfunction "2_2") (pintype "passive"))
      (node (ref "C21") (pin "2") (pinfunction "2_2") (pintype "passive"))
      (node (ref "C47") (pin "2") (pinfunction "2_2") (pintype "passive"))
      (node (ref "C5") (pin "1") (pinfunction "1_1") (pintype "passive"))
      (node (ref "D1") (pin "15") (pinfunction "VDD_IO_15") (pintype "passive"))
      (node (ref "D1") (pin "19") (pinfunction "VDD_PLL_19") (pintype "passive"))
      (node (ref "D1") (pin "20") (pinfunction "CHIP_EN_20") (pintype "passive"))
      (node (ref "D1") (pin "21") (pinfunction "VDD_BIAS_21") (pintype "passive"))
      (node (ref "D1") (pin "25") (pinfunction "VDD_LNA_25") (pintype "passive"))
      (node (ref "D1") (pin "28") (pinfunction "VDD_MIX_28") (pintype "passive"))
      (node (ref "D1") (pin "3") (pinfunction "VDD_PA_3") (pintype "passive"))
      (node (ref "D1") (pin "4") (pinfunction "VDD_BB_4") (pintype "passive"))
      (node (ref "DA1") (pin "1") (pinfunction "Vin_1") (pintype "passive"))
      (node (ref "DA1") (pin "3") (pinfunction "EN_3") (pintype "passive"))
      (node (ref "DA2") (pin "4") (pinfunction "VDD_4") (pintype "passive"))
      (node (ref "R10") (pin "2") (pinfunction "2_2") (pintype "passive"))
      (node (ref "R2") (pin "2") (pinfunction "2_2") (pintype "passive"))
      (node (ref "VT2") (pin "3") (pinfunction "D_3") (pintype "passive"))
    )
    (net (code "23") (name "GND") (class "Default")
      (node (ref "C1") (pin "2") (pinfunction "2_2") (pintype "passive"))
      (node (ref "C10") (pin "1") (pinfunction "1_1") (pintype "passive"))
      (node (ref "C11") (pin "2") (pinfunction "2_2") (pintype "passive"))
      (node (ref "C12") (pin "1") (pinfunction "1_1") (pintype "passive"))
      (node (ref "C13") (pin "1") (pinfunction "1_1") (pintype "passive"))
      (node (ref "C14") (pin "2") (pinfunction "2_2") (pintype "passive"))
      (node (ref "C15") (pin "1") (pinfunction "1_1") (pintype "passive"))
      (node (ref "C16") (pin "2") (pinfunction "2_2") (pintype "passive"))
      (node (ref "C17") (pin "1") (pinfunction "1_1") (pintype "passive"))
      (node (ref "C18") (pin "1") (pinfunction "1_1") (pintype "passive"))
      (node (ref "C19") (pin "1") (pinfunction "1_1") (pintype "passive"))
      (node (ref "C2") (pin "1") (pinfunction "1_1") (pintype "passive"))
      (node (ref "C20") (pin "1") (pinfunction "1_1") (pintype "passive"))
      (node (ref "C21") (pin "1") (pinfunction "1_1") (pintype "passive"))
      (node (ref "C22") (pin "2") (pinfunction "2_2") (pintype "passive"))
      (node (ref "C23") (pin "1") (pinfunction "1_1") (pintype "passive"))
      (node (ref "C25") (pin "1") (pinfunction "1_1") (pintype "passive"))
      (node (ref "C26") (pin "1") (pinfunction "1_1") (pintype "passive"))
      (node (ref "C28") (pin "1") (pinfunction "1_1") (pintype "passive"))
      (node (ref "C3") (pin "1") (pinfunction "1_1") (pintype "passive"))
      (node (ref "C31") (pin "1") (pinfunction "1_1") (pintype "passive"))
      (node (ref "C34") (pin "1") (pinfunction "1_1") (pintype "passive"))
      (node (ref "C35") (pin "1") (pinfunction "1_1") (pintype "passive"))
      (node (ref "C36") (pin "2") (pinfunction "2_2") (pintype "passive"))
      (node (ref "C38") (pin "2") (pinfunction "2_2") (pintype "passive"))
      (node (ref "C39") (pin "2") (pinfunction "2_2") (pintype "passive"))
      (node (ref "C4") (pin "1") (pinfunction "1_1") (pintype "passive"))
      (node (ref "C41") (pin "2") (pinfunction "2_2") (pintype "passive"))
      (node (ref "C42") (pin "2") (pinfunction "2_2") (pintype "passive"))
      (node (ref "C43") (pin "2") (pinfunction "2_2") (pintype "passive"))
      (node (ref "C44") (pin "2") (pinfunction "2_2") (pintype "passive"))
      (node (ref "C45") (pin "2") (pinfunction "2_2") (pintype "passive"))
      (node (ref "C47") (pin "1") (pinfunction "1_1") (pintype "passive"))
      (node (ref "C49") (pin "2") (pinfunction "2_2") (pintype "passive"))
      (node (ref "C5") (pin "2") (pinfunction "2_2") (pintype "passive"))
      (node (ref "C50") (pin "2") (pinfunction "2_2") (pintype "passive"))
      (node (ref "C51") (pin "2") (pinfunction "2_2") (pintype "passive"))
      (node (ref "C52") (pin "2") (pinfunction "2_2") (pintype "passive"))
      (node (ref "C53") (pin "2") (pinfunction "2_2") (pintype "passive"))
      (node (ref "C54") (pin "2") (pinfunction "2_2") (pintype "passive"))
      (node (ref "C55") (pin "2") (pinfunction "2_2") (pintype "passive"))
      (node (ref "C56") (pin "1") (pinfunction "1_1") (pintype "passive"))
      (node (ref "C57") (pin "1") (pinfunction "1_1") (pintype "passive"))
      (node (ref "C58") (pin "2") (pinfunction "2_2") (pintype "passive"))
      (node (ref "C6") (pin "1") (pinfunction "1_1") (pintype "passive"))
      (node (ref "C7") (pin "2") (pinfunction "2_2") (pintype "passive"))
      (node (ref "C8") (pin "1") (pinfunction "1_1") (pintype "passive"))
      (node (ref "C9") (pin "1") (pinfunction "1_1") (pintype "passive"))
      (node (ref "D1") (pin "14") (pinfunction "GND_IO_14") (pintype "passive"))
      (node (ref "D1") (pin "17") (pinfunction "VDDQ_17") (pintype "passive"))
      (node (ref "D1") (pin "29") (pinfunction "GND_PA_29") (pintype "passive"))
      (node (ref "D1") (pin "32") (pinfunction "GND_PA_32") (pintype "passive"))
      (node (ref "D1") (pin "33") (pinfunction "PPAD_33") (pintype "passive"))
      (node (ref "DA1") (pin "2") (pinfunction "GND_2") (pintype "passive"))
      (node (ref "DA2") (pin "2") (pinfunction "GND_2") (pintype "passive"))
      (node (ref "DD1") (pin "16") (pinfunction "VSS_16") (pintype "power_in"))
      (node (ref "DD1") (pin "31") (pinfunction "BOOT0_31") (pintype "passive"))
      (node (ref "DD1") (pin "32") (pinfunction "VSS_32") (pintype "power_in"))
      (node (ref "DD1") (pin "33") (pinfunction "PPAD_33") (pintype "power_in"))
      (node (ref "GB1") (pin "2") (pinfunction "2_2") (pintype "passive"))
      (node (ref "HL1") (pin "2") (pinfunction "2_2") (pintype "passive"))
      (node (ref "L10") (pin "1") (pinfunction "1_1") (pintype "passive"))
      (node (ref "L13") (pin "1") (pinfunction "1_1") (pintype "passive"))
      (node (ref "L4") (pin "2") (pinfunction "2_2") (pintype "passive"))
      (node (ref "L5") (pin "1") (pinfunction "1_1") (pintype "passive"))
      (node (ref "R3") (pin "1") (pinfunction "1_1") (pintype "passive"))
      (node (ref "R5") (pin "2") (pinfunction "2_2") (pintype "passive"))
      (node (ref "R7") (pin "1") (pinfunction "1_1") (pintype "passive"))
      (node (ref "SW1") (pin "1_1") (pinfunction "1_1_1") (pintype "passive"))
      (node (ref "SW1") (pin "1_2") (pinfunction "1_1_2") (pintype "passive"))
      (node (ref "U1") (pin "1") (pinfunction "GND_1") (pintype "power_in"))
      (node (ref "U1") (pin "7") (pinfunction "GND_7") (pintype "power_in"))
      (node (ref "U2") (pin "2") (pinfunction "VSS_2") (pintype "bidirectional"))
      (node (ref "U2") (pin "4") (pinfunction "R_4") (pintype "bidirectional"))
      (node (ref "U2") (pin "DIEPAD") (pinfunction "DIEPAD_DIEPAD") (pintype "bidirectional"))
      (node (ref "U3") (pin "2") (pinfunction "VSS_2") (pintype "power_in"))
      (node (ref "U4") (pin "2") (pinfunction "A1_2") (pintype "bidirectional"))
      (node (ref "U4") (pin "5") (pinfunction "A2_5") (pintype "bidirectional"))
      (node (ref "VR1") (pin "2") (pinfunction "GND_2") (pintype "passive"))
      (node (ref "VT1") (pin "2") (pinfunction "2_2") (pintype "passive"))
      (node (ref "X1") (pin "2") (pinfunction "2_2") (pintype "passive"))
      (node (ref "X2") (pin "10") (pinfunction "10_10") (pintype "passive"))
      (node (ref "X2") (pin "11") (pinfunction "11_11") (pintype "passive"))
      (node (ref "X2") (pin "5") (pinfunction "5_5") (pintype "passive"))
      (node (ref "X2") (pin "6") (pinfunction "6_6") (pintype "passive"))
      (node (ref "X2") (pin "7") (pinfunction "7_7") (pintype "passive"))
      (node (ref "X2") (pin "8") (pinfunction "8_8") (pintype "passive"))
      (node (ref "X2") (pin "9") (pinfunction "9_9") (pintype "passive"))
      (node (ref "ZQ1") (pin "1") (pinfunction "GND_1") (pintype "passive"))
      (node (ref "ZQ1") (pin "2") (pinfunction "GND_2") (pintype "passive"))
    )
    (net (code "24") (name "Net-(C29-Pad2)") (class "Default")
      (node (ref "C29") (pin "2") (pinfunction "2_2") (pintype "passive"))
      (node (ref "L8") (pin "1") (pinfunction "1_1") (pintype "passive"))
    )
    (net (code "25") (name "Net-(C30-Pad2)") (class "Default")
      (node (ref "C30") (pin "2") (pinfunction "2_2") (pintype "passive"))
      (node (ref "C33") (pin "1") (pinfunction "1_1") (pintype "passive"))
      (node (ref "L10") (pin "2") (pinfunction "2_2") (pintype "passive"))
    )
    (net (code "26") (name "Net-(C32-Pad2)") (class "Default")
      (node (ref "C32") (pin "2") (pinfunction "2_2") (pintype "passive"))
      (node (ref "L11") (pin "1") (pinfunction "1_1") (pintype "passive"))
    )
    (net (code "27") (name "Net-(C33-Pad2)") (class "Default")
      (node (ref "C33") (pin "2") (pinfunction "2_2") (pintype "passive"))
      (node (ref "C35") (pin "2") (pinfunction "2_2") (pintype "passive"))
      (node (ref "C38") (pin "1") (pinfunction "1_1") (pintype "passive"))
      (node (ref "C40") (pin "1") (pinfunction "1_1") (pintype "passive"))
      (node (ref "L9") (pin "2") (pinfunction "2_2") (pintype "passive"))
    )
    (net (code "28") (name "Net-(C34-Pad2)") (class "Default")
      (node (ref "C34") (pin "2") (pinfunction "2_2") (pintype "passive"))
      (node (ref "L12") (pin "1") (pinfunction "1_1") (pintype "passive"))
      (node (ref "L8") (pin "2") (pinfunction "2_2") (pintype "passive"))
    )
    (net (code "29") (name "Net-(C36-Pad1)") (class "Default")
      (node (ref "C36") (pin "1") (pinfunction "1_1") (pintype "passive"))
      (node (ref "C37") (pin "1") (pinfunction "1_1") (pintype "passive"))
      (node (ref "L11") (pin "2") (pinfunction "2_2") (pintype "passive"))
      (node (ref "L13") (pin "2") (pinfunction "2_2") (pintype "passive"))
    )
    (net (code "30") (name "Net-(C57-Pad2)") (class "Default")
      (node (ref "C57") (pin "2") (pinfunction "2_2") (pintype "passive"))
      (node (ref "VD1") (pin "1") (pinfunction "1_1") (pintype "passive"))
      (node (ref "X1") (pin "1") (pinfunction "1_1") (pintype "passive"))
    )
    (net (code "31") (name "Net-(D1-DLDO_1.1V)") (class "Default")
      (node (ref "C25") (pin "2") (pinfunction "2_2") (pintype "passive"))
      (node (ref "D1") (pin "13") (pinfunction "DLDO_1.1V_13") (pintype "passive"))
    )
    (net (code "32") (name "Net-(D1-RX_INN)") (class "Default")
      (node (ref "C27") (pin "2") (pinfunction "2_2") (pintype "passive"))
      (node (ref "C30") (pin "1") (pinfunction "1_1") (pintype "passive"))
      (node (ref "D1") (pin "26") (pinfunction "RX_INN_26") (pintype "passive"))
      (node (ref "L5") (pin "2") (pinfunction "2_2") (pintype "passive"))
    )
    (net (code "33") (name "Net-(D1-RX_INP)") (class "Default")
      (node (ref "C27") (pin "1") (pinfunction "1_1") (pintype "passive"))
      (node (ref "C31") (pin "2") (pinfunction "2_2") (pintype "passive"))
      (node (ref "D1") (pin "27") (pinfunction "RX_INP_27") (pintype "passive"))
      (node (ref "L4") (pin "1") (pinfunction "1_1") (pintype "passive"))
      (node (ref "L9") (pin "1") (pinfunction "1_1") (pintype "passive"))
    )
    (net (code "34") (name "Net-(D1-TX_OUTN)") (class "Default")
      (node (ref "C32") (pin "1") (pinfunction "1_1") (pintype "passive"))
      (node (ref "D1") (pin "30") (pinfunction "TX_OUTN_30") (pintype "passive"))
      (node (ref "L7") (pin "2") (pinfunction "2_2") (pintype "passive"))
    )
    (net (code "35") (name "Net-(D1-TX_OUTP)") (class "Default")
      (node (ref "C29") (pin "1") (pinfunction "1_1") (pintype "passive"))
      (node (ref "D1") (pin "31") (pinfunction "TX_OUTP_31") (pintype "passive"))
      (node (ref "L6") (pin "1") (pinfunction "1_1") (pintype "passive"))
    )
    (net (code "36") (name "Net-(D1-XTAL_IN)") (class "Default")
      (node (ref "C24") (pin "2") (pinfunction "2_2") (pintype "passive"))
      (node (ref "D1") (pin "18") (pinfunction "XTAL_IN_18") (pintype "passive"))
      (node (ref "R2") (pin "1") (pinfunction "1_1") (pintype "passive"))
      (node (ref "R3") (pin "2") (pinfunction "2_2") (pintype "passive"))
    )
    (net (code "37") (name "Net-(DA1-Vout)") (class "Default")
      (node (ref "C17") (pin "2") (pinfunction "2_2") (pintype "passive"))
      (node (ref "DA1") (pin "5") (pinfunction "Vout_5") (pintype "passive"))
      (node (ref "ZQ1") (pin "4") (pinfunction "VCC_4") (pintype "passive"))
    )
    (net (code "38") (name "Net-(DA2-RF1)") (class "Default")
      (node (ref "C40") (pin "2") (pinfunction "2_2") (pintype "passive"))
      (node (ref "DA2") (pin "3") (pinfunction "RF1_3") (pintype "passive"))
    )
    (net (code "39") (name "Net-(DA2-RF2)") (class "Default")
      (node (ref "C37") (pin "2") (pinfunction "2_2") (pintype "passive"))
      (node (ref "DA2") (pin "1") (pinfunction "RF2_1") (pintype "passive"))
      (node (ref "L12") (pin "2") (pinfunction "2_2") (pintype "passive"))
    )
    (net (code "40") (name "Net-(DA2-RFC)") (class "Default")
      (node (ref "C46") (pin "1") (pinfunction "1_1") (pintype "passive"))
      (node (ref "DA2") (pin "5") (pinfunction "RFC_5") (pintype "passive"))
    )
    (net (code "41") (name "Net-(DD1-PB1)") (class "Default")
      (node (ref "C56") (pin "2") (pinfunction "2_2") (pintype "passive"))
      (node (ref "DD1") (pin "15") (pinfunction "PB1_15") (pintype "passive"))
      (node (ref "R1") (pin "1") (pinfunction "1_1") (pintype "passive"))
      (node (ref "R7") (pin "2") (pinfunction "2_2") (pintype "passive"))
    )
    (net (code "42") (name "Net-(GB1-Pad1)") (class "Default")
      (node (ref "GB1") (pin "1") (pinfunction "1_1") (pintype "passive"))
      (node (ref "SB1") (pin "1") (pinfunction "1_1") (pintype "passive"))
    )
    (net (code "43") (name "Net-(HL1-Pad1)") (class "Default")
      (node (ref "HL1") (pin "1") (pinfunction "1_1") (pintype "passive"))
      (node (ref "R6") (pin "1") (pinfunction "1_1") (pintype "passive"))
    )
    (net (code "44") (name "Net-(HL2-Pad1)") (class "Default")
      (node (ref "HL2") (pin "1") (pinfunction "1_1") (pintype "passive"))
      (node (ref "R4") (pin "2") (pinfunction "2_2") (pintype "passive"))
    )
    (net (code "45") (name "Net-(U3-PROG)") (class "Default")
      (node (ref "R5") (pin "1") (pinfunction "1_1") (pintype "passive"))
      (node (ref "U3") (pin "5") (pinfunction "PROG_5") (pintype "input"))
    )
    (net (code "46") (name "Net-(U3-STAT)") (class "Default")
      (node (ref "HL2") (pin "2") (pinfunction "2_2") (pintype "passive"))
      (node (ref "U3") (pin "1") (pinfunction "STAT_1") (pintype "input"))
    )
    (net (code "47") (name "Net-(VD2-Pad2)") (class "Default")
      (node (ref "VD2") (pin "2") (pinfunction "2_2") (pintype "passive"))
      (node (ref "X1") (pin "3") (pinfunction "3_3") (pintype "passive"))
    )
    (net (code "48") (name "Net-(VD3-Pad2)") (class "Default")
      (node (ref "VD3") (pin "2") (pinfunction "2_2") (pintype "passive"))
      (node (ref "X1") (pin "5") (pinfunction "5_5") (pintype "passive"))
    )
    (net (code "49") (name "Net-(VT2-G)") (class "Default")
      (node (ref "C48") (pin "1") (pinfunction "1_1") (pintype "passive"))
      (node (ref "R11") (pin "2") (pinfunction "2_2") (pintype "passive"))
      (node (ref "VT2") (pin "1") (pinfunction "G_1") (pintype "passive"))
    )
    (net (code "50") (name "Net-(VT2-S)") (class "Default")
      (node (ref "C48") (pin "2") (pinfunction "2_2") (pintype "passive"))
      (node (ref "R12") (pin "2") (pinfunction "2_2") (pintype "passive"))
      (node (ref "VT2") (pin "2") (pinfunction "S_2") (pintype "passive"))
    )
    (net (code "51") (name "Net-(VT3-D)") (class "Default")
      (node (ref "R13") (pin "1") (pinfunction "1_1") (pintype "passive"))
      (node (ref "VT3") (pin "3") (pinfunction "D_3") (pintype "passive"))
      (node (ref "X1") (pin "4") (pinfunction "4_4") (pintype "passive"))
    )
    (net (code "52") (name "Net-(ZQ1-OUT)") (class "Default")
      (node (ref "C24") (pin "1") (pinfunction "1_1") (pintype "passive"))
      (node (ref "ZQ1") (pin "3") (pinfunction "OUT_3") (pintype "passive"))
    )
    (net (code "53") (name "VBAT") (class "Default")
      (node (ref "C4") (pin "2") (pinfunction "2_2") (pintype "passive"))
      (node (ref "C51") (pin "1") (pinfunction "1_1") (pintype "passive"))
      (node (ref "C54") (pin "1") (pinfunction "1_1") (pintype "passive"))
      (node (ref "R1") (pin "2") (pinfunction "2_2") (pintype "passive"))
      (node (ref "R13") (pin "2") (pinfunction "2_2") (pintype "passive"))
      (node (ref "SB1") (pin "2") (pinfunction "2_2") (pintype "passive"))
      (node (ref "U3") (pin "3") (pinfunction "VBAT_3") (pintype "input"))
      (node (ref "U4") (pin "4") (pinfunction "K3_4") (pintype "bidirectional"))
      (node (ref "VD1") (pin "2") (pinfunction "2_2") (pintype "passive"))
      (node (ref "VR1") (pin "1") (pinfunction "Vin_1") (pintype "passive"))
    )
    (net (code "54") (name "VCC") (class "Default")
      (node (ref "C1") (pin "1") (pinfunction "1_1") (pintype "passive"))
      (node (ref "C3") (pin "2") (pinfunction "2_2") (pintype "passive"))
      (node (ref "C52") (pin "1") (pinfunction "1_1") (pintype "passive"))
      (node (ref "C8") (pin "2") (pinfunction "2_2") (pintype "passive"))
      (node (ref "L1") (pin "1") (pinfunction "1_1") (pintype "passive"))
      (node (ref "L2") (pin "1") (pinfunction "1_1") (pintype "passive"))
      (node (ref "L3") (pin "1") (pinfunction "1_1") (pintype "passive"))
      (node (ref "U4") (pin "1") (pinfunction "K1_1") (pintype "bidirectional"))
      (node (ref "VR1") (pin "3") (pinfunction "Vout_3") (pintype "passive"))
    )
    (net (code "55") (name "VCCA") (class "Default")
      (node (ref "C11") (pin "1") (pinfunction "1_1") (pintype "passive"))
      (node (ref "C13") (pin "2") (pinfunction "2_2") (pintype "passive"))
      (node (ref "C14") (pin "1") (pinfunction "1_1") (pintype "passive"))
      (node (ref "C16") (pin "1") (pinfunction "1_1") (pintype "passive"))
      (node (ref "C18") (pin "2") (pinfunction "2_2") (pintype "passive"))
      (node (ref "C20") (pin "2") (pinfunction "2_2") (pintype "passive"))
      (node (ref "C22") (pin "1") (pinfunction "1_1") (pintype "passive"))
      (node (ref "C6") (pin "2") (pinfunction "2_2") (pintype "passive"))
      (node (ref "C7") (pin "1") (pinfunction "1_1") (pintype "passive"))
      (node (ref "C9") (pin "2") (pinfunction "2_2") (pintype "passive"))
      (node (ref "L1") (pin "2") (pinfunction "2_2") (pintype "passive"))
      (node (ref "U1") (pin "6") (pinfunction "VDDIO_6") (pintype "power_in"))
      (node (ref "U1") (pin "8") (pinfunction "VDD_8") (pintype "power_in"))
      (node (ref "U2") (pin "1") (pinfunction "VDD_1") (pintype "bidirectional"))
      (node (ref "U2") (pin "5") (pinfunction "VDDH_5") (pintype "bidirectional"))
      (node (ref "U4") (pin "3") (pinfunction "K2_3") (pintype "bidirectional"))
    )
    (net (code "56") (name "VCC_RADIO") (class "Default")
      (node (ref "C23") (pin "2") (pinfunction "2_2") (pintype "passive"))
      (node (ref "L3") (pin "2") (pinfunction "2_2") (pintype "passive"))
      (node (ref "R12") (pin "1") (pinfunction "1_1") (pintype "passive"))
    )
    (net (code "57") (name "VDD") (class "Default")
      (node (ref "C41") (pin "1") (pinfunction "1_1") (pintype "passive"))
      (node (ref "C42") (pin "1") (pinfunction "1_1") (pintype "passive"))
      (node (ref "C43") (pin "1") (pinfunction "1_1") (pintype "passive"))
      (node (ref "C44") (pin "1") (pinfunction "1_1") (pintype "passive"))
      (node (ref "C45") (pin "1") (pinfunction "1_1") (pintype "passive"))
      (node (ref "DD1") (pin "1") (pinfunction "VDD_1") (pintype "power_in"))
      (node (ref "DD1") (pin "17") (pinfunction "VDD_17") (pintype "power_in"))
      (node (ref "DD1") (pin "5") (pinfunction "VDDA_5") (pintype "power_in"))
      (node (ref "L2") (pin "2") (pinfunction "2_2") (pintype "passive"))
      (node (ref "R14") (pin "1") (pinfunction "1_1") (pintype "passive"))
      (node (ref "R15") (pin "1") (pinfunction "1_1") (pintype "passive"))
      (node (ref "R8") (pin "2") (pinfunction "2_2") (pintype "passive"))
      (node (ref "R9") (pin "1") (pinfunction "1_1") (pintype "passive"))
      (node (ref "VT3") (pin "1") (pinfunction "G_1") (pintype "passive"))
    )
    (net (code "58") (name "unconnected-(D1-BPSK_IN-Pad6)") (class "Default")
      (node (ref "D1") (pin "6") (pinfunction "BPSK_IN_6") (pintype "passive+no_connect"))
    )
    (net (code "59") (name "unconnected-(D1-DFT_EN-Pad7)") (class "Default")
      (node (ref "D1") (pin "7") (pinfunction "DFT_EN_7") (pintype "passive+no_connect"))
    )
    (net (code "60") (name "unconnected-(D1-NC-Pad1)") (class "Default")
      (node (ref "D1") (pin "1") (pinfunction "NC_1") (pintype "passive+no_connect"))
    )
    (net (code "61") (name "unconnected-(D1-NC-Pad16)") (class "Default")
      (node (ref "D1") (pin "16") (pinfunction "NC_16") (pintype "passive+no_connect"))
    )
    (net (code "62") (name "unconnected-(D1-TMUX2-Pad24)") (class "Default")
      (node (ref "D1") (pin "24") (pinfunction "TMUX2_24") (pintype "passive+no_connect"))
    )
    (net (code "63") (name "unconnected-(D1-TMUX3-Pad23)") (class "Default")
      (node (ref "D1") (pin "23") (pinfunction "TMUX3_23") (pintype "passive+no_connect"))
    )
    (net (code "64") (name "unconnected-(D1-TMUX4-Pad22)") (class "Default")
      (node (ref "D1") (pin "22") (pinfunction "TMUX4_22") (pintype "passive+no_connect"))
    )
    (net (code "65") (name "unconnected-(DA1-N{slash}C-Pad4)") (class "Default")
      (node (ref "DA1") (pin "4") (pinfunction "N/C_4") (pintype "passive+no_connect"))
    )
    (net (code "66") (name "unconnected-(DD1-PA0-Pad6)") (class "Default")
      (node (ref "DD1") (pin "6") (pinfunction "PA0_6") (pintype "passive"))
    )
    (net (code "67") (name "unconnected-(DD1-PA1-Pad7)") (class "Default")
      (node (ref "DD1") (pin "7") (pinfunction "PA1_7") (pintype "passive"))
    )
    (net (code "68") (name "unconnected-(DD1-PA4-Pad10)") (class "Default")
      (node (ref "DD1") (pin "10") (pinfunction "PA4_10") (pintype "passive"))
    )
    (net (code "69") (name "unconnected-(DD1-PA6-Pad12)") (class "Default")
      (node (ref "DD1") (pin "12") (pinfunction "PA6_12") (pintype "passive"))
    )
    (net (code "70") (name "unconnected-(DD1-PA8-Pad18)") (class "Default")
      (node (ref "DD1") (pin "18") (pinfunction "PA8_18") (pintype "passive"))
    )
    (net (code "71") (name "unconnected-(DD1-PA12-Pad22)") (class "Default")
      (node (ref "DD1") (pin "22") (pinfunction "PA12_22") (pintype "passive"))
    )
    (net (code "72") (name "unconnected-(DD1-PA15-Pad25)") (class "Default")
      (node (ref "DD1") (pin "25") (pinfunction "PA15_25") (pintype "passive"))
    )
    (net (code "73") (name "unconnected-(DD1-PB0-Pad14)") (class "Default")
      (node (ref "DD1") (pin "14") (pinfunction "PB0_14") (pintype "passive"))
    )
    (net (code "74") (name "unconnected-(DD1-PB7-Pad30)") (class "Default")
      (node (ref "DD1") (pin "30") (pinfunction "PB7_30") (pintype "passive"))
    )
    (net (code "75") (name "unconnected-(X2-Pad2)") (class "Default")
      (node (ref "X2") (pin "2") (pinfunction "2_2") (pintype "passive"))
    )
    (net (code "76") (name "unconnected-(X2-Pad3)") (class "Default")
      (node (ref "X2") (pin "3") (pinfunction "3_3") (pintype "passive"))
    )
    (net (code "77") (name "unconnected-(X2-Pad4)") (class "Default")
      (node (ref "X2") (pin "4") (pinfunction "4_4") (pintype "passive"))
    )
  )
)
